# NCS_Wireless_Bed_Unit_DIP_Conn_Prog_conn.net
KiCad netlist of a schematic drawn in Altium Designer
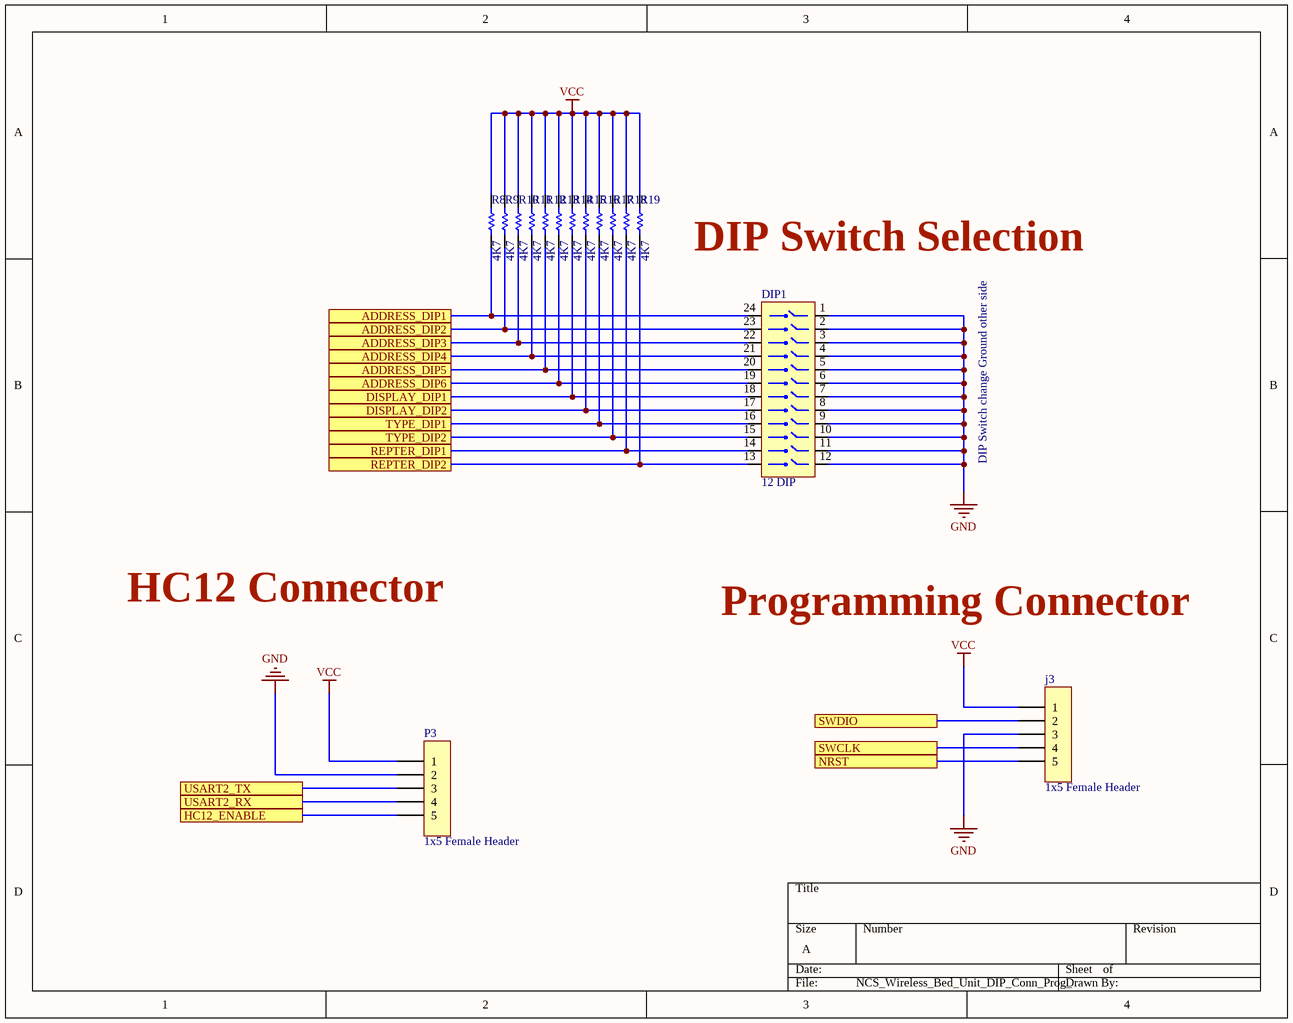
[diagram p0: NCS_Wireless_Bed_Unit_DIP_Conn_Prog_conn.SchDoc]

(export (version "E")
  (design (tool "Eeschema 10.0.6"))
  (components
    (comp (ref "DIP1")
      (value "12 DIP")
      (footprint "DIP24")
      (libsource (lib "NCS_Wireless_Bed_Unit") (part "12 Way 2.54MM DIP switch - SUNROM"))
    )
    (comp (ref "j3")
      (value "1x5 Female Header")
      (footprint "1x5 Female Header")
      (description "2.54mm (0.1) Pitch SIL Vertical PC Tail Pin Header, 6.1mm mating pin height, tin, 5 contacts\"")
      (fields (field (name "MANUFACTURER") "Harwin") (field (name "MANUFACTURER PART NUMBER") "M20-9990546"))
      (libsource (lib "schlib") (part "M20-9990546"))
    )
    (comp (ref "P3")
      (value "1x5 Female Header")
      (footprint "1x5 Female Header")
      (description "2.54mm (0.1) Pitch SIL Vertical PC Tail Pin Header, 6.1mm mating pin height, tin, 5 contacts\"")
      (fields (field (name "MANUFACTURER") "Harwin") (field (name "MANUFACTURER PART NUMBER") "M20-9990546"))
      (libsource (lib "schlib") (part "M20-9990546"))
    )
    (comp (ref "R8")
      (value "4K7")
      (footprint "RC0805FR-7W4K7L")
      (description "SMD Chip Resistor, 4.7 kOhm, ± 1%, 250 mW, 0805 [2012 Metric], Thick Film, General Purpose")
      (fields
        (field (name "MANUFACTURER") "Yageo")
        (field (name "MANUFACTURER PART NUMBER") "RC0805FR-7W4K7L")
      )
      (libsource (lib "schlib") (part "RC0805FR-7W4K7L"))
    )
    (comp (ref "R9")
      (value "4K7")
      (footprint "RC0805FR-7W4K7L")
      (description "SMD Chip Resistor, 4.7 kOhm, ± 1%, 250 mW, 0805 [2012 Metric], Thick Film, General Purpose")
      (fields
        (field (name "MANUFACTURER") "Yageo")
        (field (name "MANUFACTURER PART NUMBER") "RC0805FR-7W4K7L")
      )
      (libsource (lib "schlib") (part "RC0805FR-7W4K7L"))
    )
    (comp (ref "R10")
      (value "4K7")
      (footprint "RC0805FR-7W4K7L")
      (description "SMD Chip Resistor, 4.7 kOhm, ± 1%, 250 mW, 0805 [2012 Metric], Thick Film, General Purpose")
      (fields
        (field (name "MANUFACTURER") "Yageo")
        (field (name "MANUFACTURER PART NUMBER") "RC0805FR-7W4K7L")
      )
      (libsource (lib "schlib") (part "RC0805FR-7W4K7L"))
    )
    (comp (ref "R11")
      (value "4K7")
      (footprint "RC0805FR-7W4K7L")
      (description "SMD Chip Resistor, 4.7 kOhm, ± 1%, 250 mW, 0805 [2012 Metric], Thick Film, General Purpose")
      (fields
        (field (name "MANUFACTURER") "Yageo")
        (field (name "MANUFACTURER PART NUMBER") "RC0805FR-7W4K7L")
      )
      (libsource (lib "schlib") (part "RC0805FR-7W4K7L"))
    )
    (comp (ref "R12")
      (value "4K7")
      (footprint "RC0805FR-7W4K7L")
      (description "SMD Chip Resistor, 4.7 kOhm, ± 1%, 250 mW, 0805 [2012 Metric], Thick Film, General Purpose")
      (fields
        (field (name "MANUFACTURER") "Yageo")
        (field (name "MANUFACTURER PART NUMBER") "RC0805FR-7W4K7L")
      )
      (libsource (lib "schlib") (part "RC0805FR-7W4K7L"))
    )
    (comp (ref "R13")
      (value "4K7")
      (footprint "RC0805FR-7W4K7L")
      (description "SMD Chip Resistor, 4.7 kOhm, ± 1%, 250 mW, 0805 [2012 Metric], Thick Film, General Purpose")
      (fields
        (field (name "MANUFACTURER") "Yageo")
        (field (name "MANUFACTURER PART NUMBER") "RC0805FR-7W4K7L")
      )
      (libsource (lib "schlib") (part "RC0805FR-7W4K7L"))
    )
    (comp (ref "R14")
      (value "4K7")
      (footprint "RC0805FR-7W4K7L")
      (description "SMD Chip Resistor, 4.7 kOhm, ± 1%, 250 mW, 0805 [2012 Metric], Thick Film, General Purpose")
      (fields
        (field (name "MANUFACTURER") "Yageo")
        (field (name "MANUFACTURER PART NUMBER") "RC0805FR-7W4K7L")
      )
      (libsource (lib "schlib") (part "RC0805FR-7W4K7L"))
    )
    (comp (ref "R15")
      (value "4K7")
      (footprint "RC0805FR-7W4K7L")
      (description "SMD Chip Resistor, 4.7 kOhm, ± 1%, 250 mW, 0805 [2012 Metric], Thick Film, General Purpose")
      (fields
        (field (name "MANUFACTURER") "Yageo")
        (field (name "MANUFACTURER PART NUMBER") "RC0805FR-7W4K7L")
      )
      (libsource (lib "schlib") (part "RC0805FR-7W4K7L"))
    )
    (comp (ref "R16")
      (value "4K7")
      (footprint "RC0805FR-7W4K7L")
      (description "SMD Chip Resistor, 4.7 kOhm, ± 1%, 250 mW, 0805 [2012 Metric], Thick Film, General Purpose")
      (fields
        (field (name "MANUFACTURER") "Yageo")
        (field (name "MANUFACTURER PART NUMBER") "RC0805FR-7W4K7L")
      )
      (libsource (lib "schlib") (part "RC0805FR-7W4K7L"))
    )
    (comp (ref "R17")
      (value "4K7")
      (footprint "RC0805FR-7W4K7L")
      (description "SMD Chip Resistor, 4.7 kOhm, ± 1%, 250 mW, 0805 [2012 Metric], Thick Film, General Purpose")
      (fields
        (field (name "MANUFACTURER") "Yageo")
        (field (name "MANUFACTURER PART NUMBER") "RC0805FR-7W4K7L")
      )
      (libsource (lib "schlib") (part "RC0805FR-7W4K7L"))
    )
    (comp (ref "R18")
      (value "4K7")
      (footprint "RC0805FR-7W4K7L")
      (description "SMD Chip Resistor, 4.7 kOhm, ± 1%, 250 mW, 0805 [2012 Metric], Thick Film, General Purpose")
      (fields
        (field (name "MANUFACTURER") "Yageo")
        (field (name "MANUFACTURER PART NUMBER") "RC0805FR-7W4K7L")
      )
      (libsource (lib "schlib") (part "RC0805FR-7W4K7L"))
    )
    (comp (ref "R19")
      (value "4K7")
      (footprint "RC0805FR-7W4K7L")
      (description "SMD Chip Resistor, 4.7 kOhm, ± 1%, 250 mW, 0805 [2012 Metric], Thick Film, General Purpose")
      (fields
        (field (name "MANUFACTURER") "Yageo")
        (field (name "MANUFACTURER PART NUMBER") "RC0805FR-7W4K7L")
      )
      (libsource (lib "schlib") (part "RC0805FR-7W4K7L"))
    )
  )
  (nets
    (net (code "1") (name "/ADDRESS_DIP1") (class "Default")
      (node (ref "DIP1") (pin "24") (pinfunction "24_24") (pintype "passive"))
      (node (ref "R8") (pin "2") (pinfunction "2_2") (pintype "passive"))
    )
    (net (code "2") (name "/ADDRESS_DIP2") (class "Default")
      (node (ref "DIP1") (pin "23") (pinfunction "23_23") (pintype "passive"))
      (node (ref "R9") (pin "2") (pinfunction "2_2") (pintype "passive"))
    )
    (net (code "3") (name "/ADDRESS_DIP3") (class "Default")
      (node (ref "DIP1") (pin "22") (pinfunction "22_22") (pintype "passive"))
      (node (ref "R10") (pin "2") (pinfunction "2_2") (pintype "passive"))
    )
    (net (code "4") (name "/ADDRESS_DIP4") (class "Default")
      (node (ref "DIP1") (pin "21") (pinfunction "21_21") (pintype "passive"))
      (node (ref "R11") (pin "2") (pinfunction "2_2") (pintype "passive"))
    )
    (net (code "5") (name "/ADDRESS_DIP5") (class "Default")
      (node (ref "DIP1") (pin "20") (pinfunction "20_20") (pintype "passive"))
      (node (ref "R12") (pin "2") (pinfunction "2_2") (pintype "passive"))
    )
    (net (code "6") (name "/ADDRESS_DIP6") (class "Default")
      (node (ref "DIP1") (pin "19") (pinfunction "19_19") (pintype "passive"))
      (node (ref "R13") (pin "2") (pinfunction "2_2") (pintype "passive"))
    )
    (net (code "7") (name "/DISPLAY_DIP1") (class "Default")
      (node (ref "DIP1") (pin "18") (pinfunction "18_18") (pintype "passive"))
      (node (ref "R14") (pin "2") (pinfunction "2_2") (pintype "passive"))
    )
    (net (code "8") (name "/DISPLAY_DIP2") (class "Default")
      (node (ref "DIP1") (pin "17") (pinfunction "17_17") (pintype "passive"))
      (node (ref "R15") (pin "2") (pinfunction "2_2") (pintype "passive"))
    )
    (net (code "9") (name "/HC12_ENABLE") (class "Default")
      (node (ref "P3") (pin "5") (pinfunction "5_5") (pintype "passive"))
    )
    (net (code "10") (name "/NRST") (class "Default")
      (node (ref "j3") (pin "5") (pinfunction "5_5") (pintype "passive"))
    )
    (net (code "11") (name "/REPTER_DIP1") (class "Default")
      (node (ref "DIP1") (pin "14") (pinfunction "14_14") (pintype "passive"))
      (node (ref "R18") (pin "2") (pinfunction "2_2") (pintype "passive"))
    )
    (net (code "12") (name "/REPTER_DIP2") (class "Default")
      (node (ref "DIP1") (pin "13") (pinfunction "13_13") (pintype "passive"))
      (node (ref "R19") (pin "2") (pinfunction "2_2") (pintype "passive"))
    )
    (net (code "13") (name "/SWCLK") (class "Default")
      (node (ref "j3") (pin "4") (pinfunction "4_4") (pintype "passive"))
    )
    (net (code "14") (name "/SWDIO") (class "Default")
      (node (ref "j3") (pin "2") (pinfunction "2_2") (pintype "passive"))
    )
    (net (code "15") (name "/TYPE_DIP1") (class "Default")
      (node (ref "DIP1") (pin "16") (pinfunction "16_16") (pintype "passive"))
      (node (ref "R16") (pin "2") (pinfunction "2_2") (pintype "passive"))
    )
    (net (code "16") (name "/TYPE_DIP2") (class "Default")
      (node (ref "DIP1") (pin "15") (pinfunction "15_15") (pintype "passive"))
      (node (ref "R17") (pin "2") (pinfunction "2_2") (pintype "passive"))
    )
    (net (code "17") (name "/USART2_RX") (class "Default")
      (node (ref "P3") (pin "4") (pinfunction "4_4") (pintype "passive"))
    )
    (net (code "18") (name "/USART2_TX") (class "Default")
      (node (ref "P3") (pin "3") (pinfunction "3_3") (pintype "passive"))
    )
    (net (code "19") (name "GND") (class "Default")
      (node (ref "DIP1") (pin "1") (pinfunction "1_1") (pintype "passive"))
      (node (ref "DIP1") (pin "10") (pinfunction "10_10") (pintype "passive"))
      (node (ref "DIP1") (pin "11") (pinfunction "11_11") (pintype "passive"))
      (node (ref "DIP1") (pin "12") (pinfunction "12_12") (pintype "passive"))
      (node (ref "DIP1") (pin "2") (pinfunction "2_2") (pintype "passive"))
      (node (ref "DIP1") (pin "3") (pinfunction "3_3") (pintype "passive"))
      (node (ref "DIP1") (pin "4") (pinfunction "4_4") (pintype "passive"))
      (node (ref "DIP1") (pin "5") (pinfunction "5_5") (pintype "passive"))
      (node (ref "DIP1") (pin "6") (pinfunction "6_6") (pintype "passive"))
      (node (ref "DIP1") (pin "7") (pinfunction "7_7") (pintype "passive"))
      (node (ref "DIP1") (pin "8") (pinfunction "8_8") (pintype "passive"))
      (node (ref "DIP1") (pin "9") (pinfunction "9_9") (pintype "passive"))
      (node (ref "P3") (pin "2") (pinfunction "2_2") (pintype "passive"))
      (node (ref "j3") (pin "3") (pinfunction "3_3") (pintype "passive"))
    )
    (net (code "20") (name "VCC") (class "Default")
      (node (ref "P3") (pin "1") (pinfunction "1_1") (pintype "passive"))
      (node (ref "R10") (pin "1") (pinfunction "1_1") (pintype "passive"))
      (node (ref "R11") (pin "1") (pinfunction "1_1") (pintype "passive"))
      (node (ref "R12") (pin "1") (pinfunction "1_1") (pintype "passive"))
      (node (ref "R13") (pin "1") (pinfunction "1_1") (pintype "passive"))
      (node (ref "R14") (pin "1") (pinfunction "1_1") (pintype "passive"))
      (node (ref "R15") (pin "1") (pinfunction "1_1") (pintype "passive"))
      (node (ref "R16") (pin "1") (pinfunction "1_1") (pintype "passive"))
      (node (ref "R17") (pin "1") (pinfunction "1_1") (pintype "passive"))
      (node (ref "R18") (pin "1") (pinfunction "1_1") (pintype "passive"))
      (node (ref "R19") (pin "1") (pinfunction "1_1") (pintype "passive"))
      (node (ref "R8") (pin "1") (pinfunction "1_1") (pintype "passive"))
      (node (ref "R9") (pin "1") (pinfunction "1_1") (pintype "passive"))
      (node (ref "j3") (pin "1") (pinfunction "1_1") (pintype "passive"))
    )
  )
)
